# Current-Probe_Topsheet.net
KiCad netlist of a schematic drawn in Altium Designer
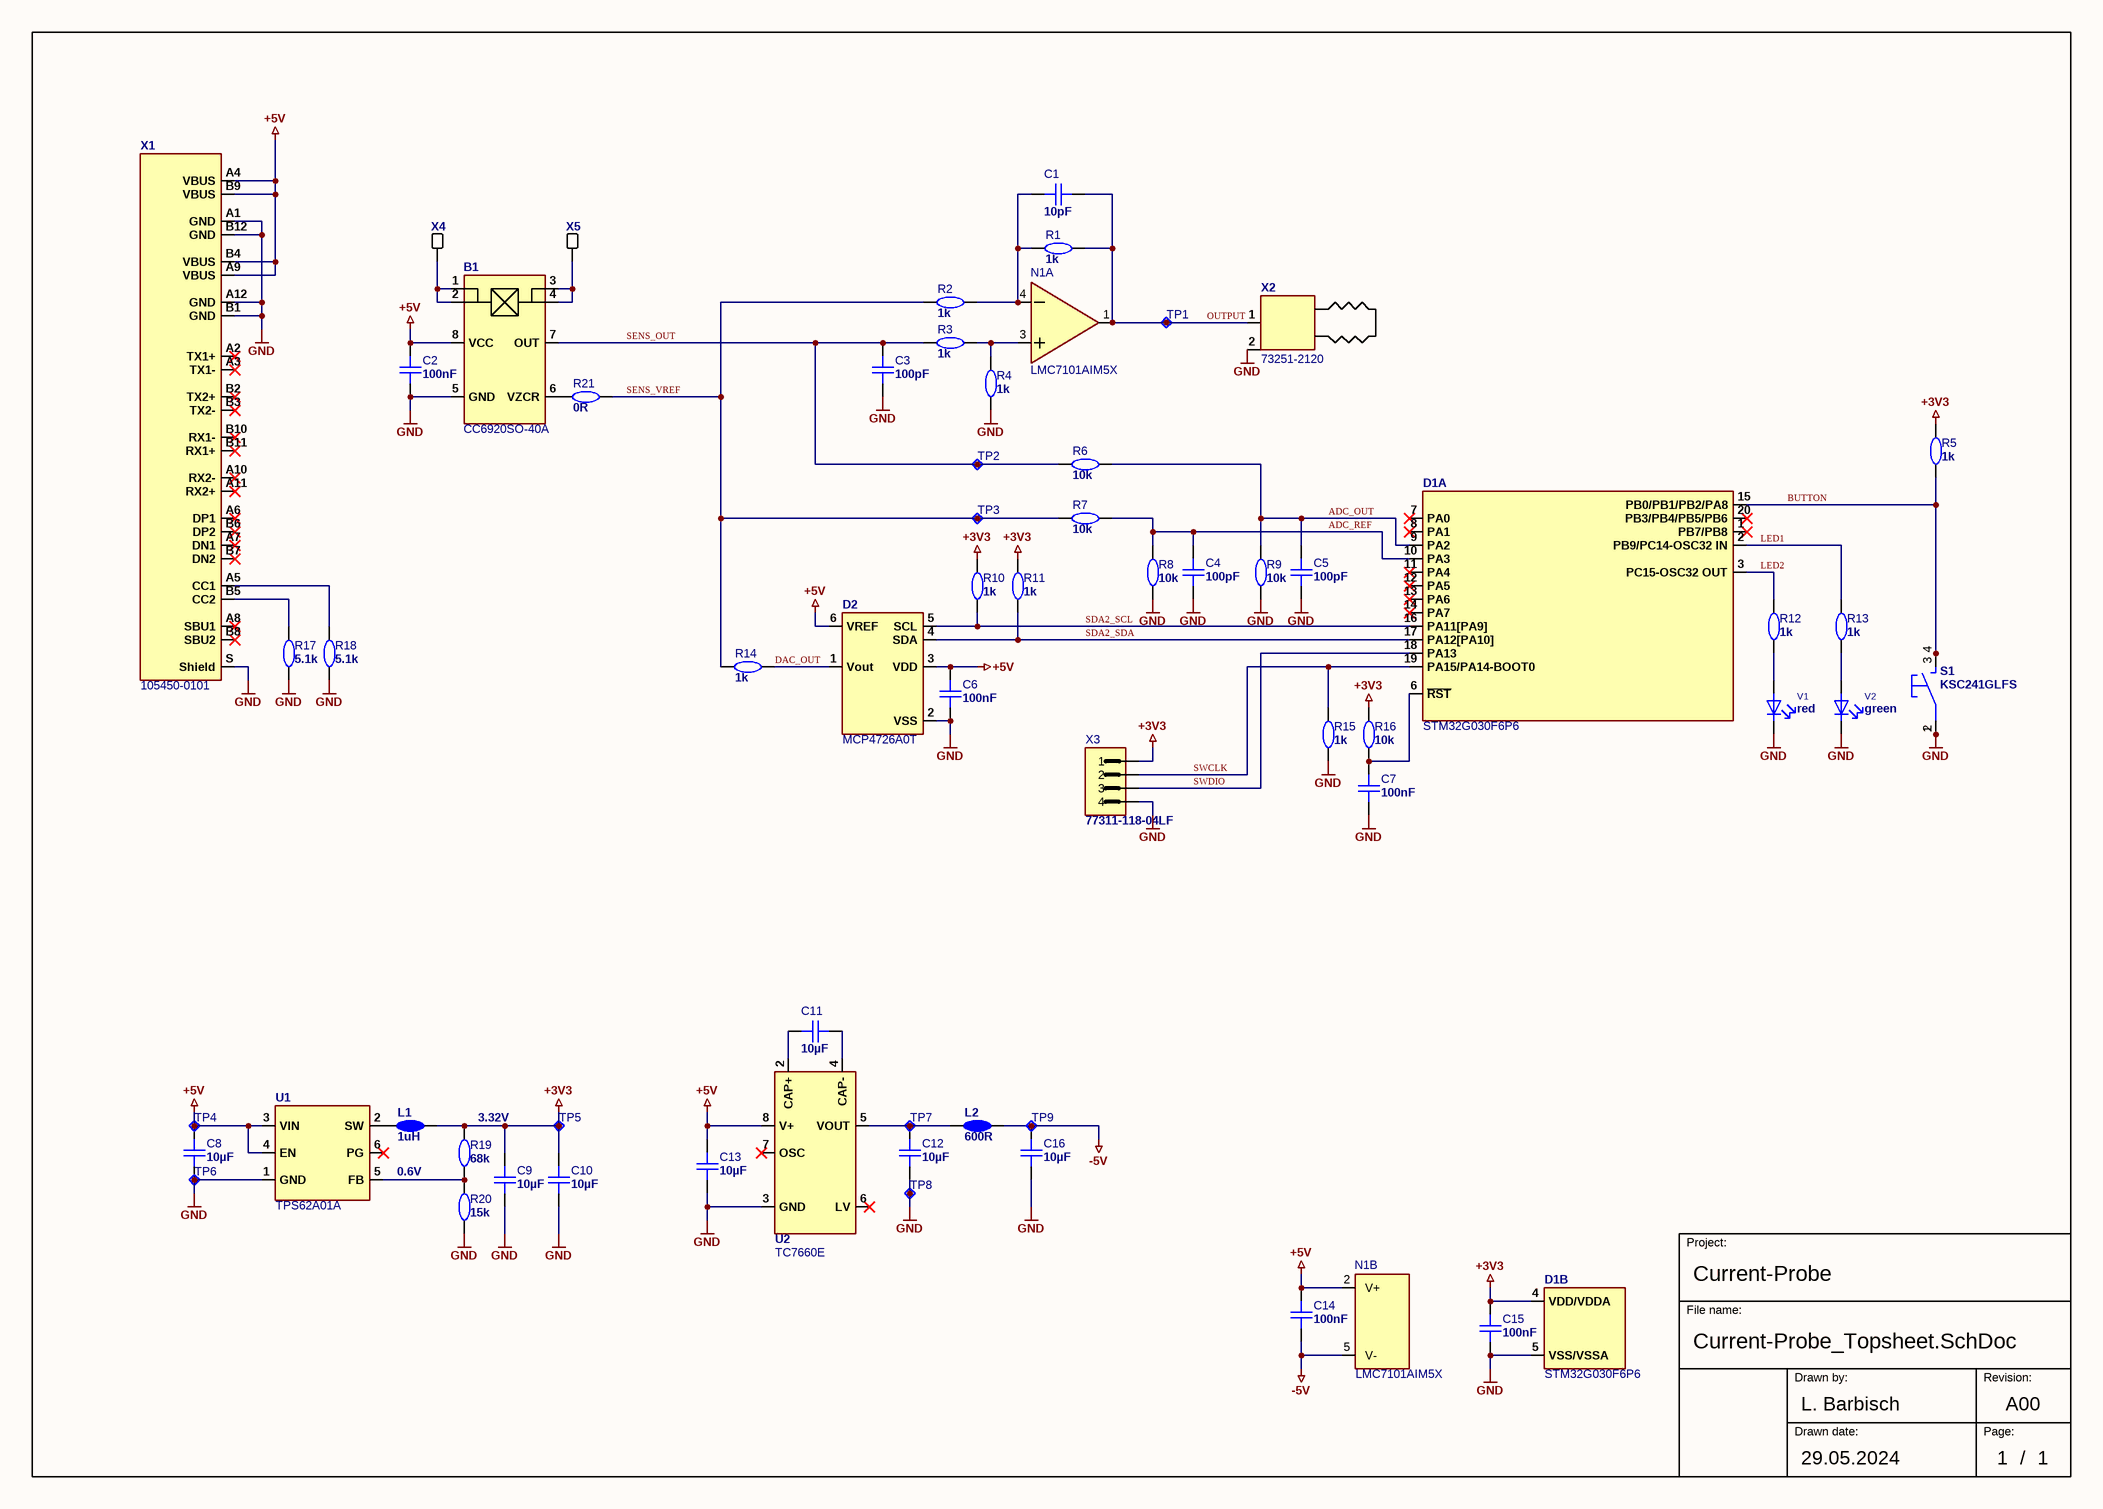
[diagram p0: Current-Probe_Topsheet.SchDoc]

(export (version "E")
  (design (tool "Eeschema 10.0.6"))
  (components
    (comp (ref "B1")
      (value "CC6920SO-40A")
      (footprint "SOIC8_N_RF")
      (description "IC Current sensor ±40A 5V")
      (fields (field (name "MANUFACTURER") "Cross chip"))
      (libsource (lib "Global Library") (part "CC6920SO-40A"))
    )
    (comp (ref "C1")
      (value "10pF")
      (footprint "C-0603_1608_095_L_RF")
      (description "Cap Cer SMD 10p 50V +/- 0.25pF  0603 C0G")
      (fields
        (field (name "MANUFACTURER PART NUMBER") "06035A100CAT*")
        (field (name "MANUFACTURER") "AVX")
        (field (name "USER") "zupa")
      )
      (libsource (lib "GPV Switzerland SA") (part "CAP"))
    )
    (comp (ref "C2")
      (value "100nF")
      (footprint "C-0603_1608_095_L_RF")
      (description "Cap Cer SMD 100n 50V 10% 0603 X7R")
      (fields
        (field (name "MANUFACTURER") "KEMET")
        (field (name "MANUFACTURER PART NUMBER") "C0603C104K5RAC")
        (field (name "USER") "epph")
      )
      (libsource (lib "GPV Switzerland SA") (part "CAP"))
    )
    (comp (ref "C3")
      (value "100pF")
      (footprint "C-0603_1608_095_L_RF")
      (description "Cap Cer SMD 100p 50V 5% 0603 C0G")
      (fields
        (field (name "MANUFACTURER PART NUMBER") "CC0603J*NPO9BN101")
        (field (name "MANUFACTURER") "YAGEO")
        (field (name "USER") "zupa")
      )
      (libsource (lib "GPV Switzerland SA") (part "CAP"))
    )
    (comp (ref "C4")
      (value "100pF")
      (footprint "C-0603_1608_095_L_RF")
      (description "Cap Cer SMD 100p 50V 5% 0603 C0G")
      (fields
        (field (name "MANUFACTURER PART NUMBER") "CC0603J*NPO9BN101")
        (field (name "MANUFACTURER") "YAGEO")
        (field (name "USER") "zupa")
      )
      (libsource (lib "GPV Switzerland SA") (part "CAP"))
    )
    (comp (ref "C5")
      (value "100pF")
      (footprint "C-0603_1608_095_L_RF")
      (description "Cap Cer SMD 100p 50V 5% 0603 C0G")
      (fields
        (field (name "MANUFACTURER PART NUMBER") "CC0603J*NPO9BN101")
        (field (name "MANUFACTURER") "YAGEO")
        (field (name "USER") "zupa")
      )
      (libsource (lib "GPV Switzerland SA") (part "CAP"))
    )
    (comp (ref "C6")
      (value "100nF")
      (footprint "C-0603_1608_095_L_RF")
      (description "Cap Cer SMD 100n 50V 10% 0603 X7R")
      (fields
        (field (name "MANUFACTURER") "KEMET")
        (field (name "MANUFACTURER PART NUMBER") "C0603C104K5RAC")
        (field (name "USER") "epph")
      )
      (libsource (lib "GPV Switzerland SA") (part "CAP"))
    )
    (comp (ref "C7")
      (value "100nF")
      (footprint "C-0603_1608_095_L_RF")
      (description "Cap Cer SMD 100n 50V 10% 0603 X7R")
      (fields
        (field (name "MANUFACTURER") "KEMET")
        (field (name "MANUFACTURER PART NUMBER") "C0603C104K5RAC")
        (field (name "USER") "epph")
      )
      (libsource (lib "GPV Switzerland SA") (part "CAP"))
    )
    (comp (ref "C8")
      (value "10µF")
      (footprint "C-0805_2012_155_L_RF")
      (description "Cap Cer SMD 10u 16V 10% 0805 X7R")
      (fields
        (field (name "MANUFACTURER") "Yageo")
        (field (name "MANUFACTURER PART NUMBER") "CC0805KKX7R7BB106")
        (field (name "USER") "epph")
      )
      (libsource (lib "GPV Switzerland SA") (part "CAP"))
    )
    (comp (ref "C9")
      (value "10µF")
      (footprint "C-0805_2012_155_L_RF")
      (description "Cap Cer SMD 10u 16V 10% 0805 X7R")
      (fields
        (field (name "MANUFACTURER") "Yageo")
        (field (name "MANUFACTURER PART NUMBER") "CC0805KKX7R7BB106")
        (field (name "USER") "epph")
      )
      (libsource (lib "GPV Switzerland SA") (part "CAP"))
    )
    (comp (ref "C10")
      (value "10µF")
      (footprint "C-0805_2012_155_L_RF")
      (description "Cap Cer SMD 10u 16V 10% 0805 X7R")
      (fields
        (field (name "MANUFACTURER") "Yageo")
        (field (name "MANUFACTURER PART NUMBER") "CC0805KKX7R7BB106")
        (field (name "USER") "epph")
      )
      (libsource (lib "GPV Switzerland SA") (part "CAP"))
    )
    (comp (ref "C11")
      (value "10µF")
      (footprint "C-0805_2012_155_L_RF")
      (description "Cap Cer SMD 10u 16V 10% 0805 X7R")
      (fields
        (field (name "MANUFACTURER") "Yageo")
        (field (name "MANUFACTURER PART NUMBER") "CC0805KKX7R7BB106")
        (field (name "USER") "epph")
      )
      (libsource (lib "GPV Switzerland SA") (part "CAP"))
    )
    (comp (ref "C12")
      (value "10µF")
      (footprint "C-0805_2012_155_L_RF")
      (description "Cap Cer SMD 10u 16V 10% 0805 X7R")
      (fields
        (field (name "MANUFACTURER") "Yageo")
        (field (name "MANUFACTURER PART NUMBER") "CC0805KKX7R7BB106")
        (field (name "USER") "epph")
      )
      (libsource (lib "GPV Switzerland SA") (part "CAP"))
    )
    (comp (ref "C13")
      (value "10µF")
      (footprint "C-0805_2012_155_L_RF")
      (description "Cap Cer SMD 10u 16V 10% 0805 X7R")
      (fields
        (field (name "MANUFACTURER") "Yageo")
        (field (name "MANUFACTURER PART NUMBER") "CC0805KKX7R7BB106")
        (field (name "USER") "epph")
      )
      (libsource (lib "GPV Switzerland SA") (part "CAP"))
    )
    (comp (ref "C14")
      (value "100nF")
      (footprint "C-0603_1608_095_L_RF")
      (description "Cap Cer SMD 100n 50V 10% 0603 X7R")
      (fields
        (field (name "MANUFACTURER") "KEMET")
        (field (name "MANUFACTURER PART NUMBER") "C0603C104K5RAC")
        (field (name "USER") "epph")
      )
      (libsource (lib "GPV Switzerland SA") (part "CAP"))
    )
    (comp (ref "C15")
      (value "100nF")
      (footprint "C-0603_1608_095_L_RF")
      (description "Cap Cer SMD 100n 50V 10% 0603 X7R")
      (fields
        (field (name "MANUFACTURER") "KEMET")
        (field (name "MANUFACTURER PART NUMBER") "C0603C104K5RAC")
        (field (name "USER") "epph")
      )
      (libsource (lib "GPV Switzerland SA") (part "CAP"))
    )
    (comp (ref "C16")
      (value "10µF")
      (footprint "C-0805_2012_155_L_RF")
      (description "Cap Cer SMD 10u 16V 10% 0805 X7R")
      (fields
        (field (name "MANUFACTURER") "Yageo")
        (field (name "MANUFACTURER PART NUMBER") "CC0805KKX7R7BB106")
        (field (name "USER") "epph")
      )
      (libsource (lib "GPV Switzerland SA") (part "CAP"))
    )
    (comp (ref "D1")
      (value "STM32G030F6P6")
      (footprint "TSSOP20_N_RF")
      (description "IC MCU Cortex M0+ 32K Flash, 8K RAM, 64MHz")
      (fields (field (name "MANUFACTURER") "ST"))
      (libsource (lib "Global Library") (part "STM32G030F6P6"))
    )
    (comp (ref "D2")
      (value "MCP4726A0T")
      (footprint "SOT23-6_N_RF")
      (description "IC DAC I2C 12Bit 2.7V-5.5V")
      (fields (field (name "MANUFACTURER") "Microchip"))
      (libsource (lib "Global Library") (part "MCP4726A0T"))
    )
    (comp (ref "L1")
      (value "1uH")
      (footprint "L_0805_N_RF")
      (description "Inductor 1uH 0.95A")
      (fields
        (field (name "MANUFACTURER") "Sunlord")
        (field (name "MANUFACTURER PART NUMBER") "MPH201210S1R0")
      )
      (libsource (lib "Global Library") (part "MPH201210S1R0"))
    )
    (comp (ref "L2")
      (value "600R")
      (footprint "L_0805_N_RF")
      (description "Ferrite Bead 600Ohm 2A 0805")
      (fields
        (field (name "MANUFACTURER") "Würth")
        (field (name "MANUFACTURER PART NUMBER") "782853611")
        (field (name "PART_VALIDATED") "Yes ¦ No")
        (field (name "FOOTPRINT_VALIDATED") "Yes ¦ No")
      )
      (libsource (lib "Global Library") (part "782853611"))
    )
    (comp (ref "N1")
      (value "LMC7101AIM5X")
      (footprint "SOT23-5_L_RF")
      (description "Low Power OP Rail to Rail")
      (fields (field (name "MANUFACTURER") "Texas Instrument") (field (name "USER") "zupa"))
      (libsource (lib "") (part "LMC7101AIM5X_1"))
    )
    (comp (ref "R1")
      (value "1k")
      (footprint "R-0603_1608_050_L_RF")
      (description "Res SMD 1k 1% 0.1W 0603")
      (fields
        (field (name "MANUFACTURER") "YAGEO")
        (field (name "MANUFACTURER PART NUMBER") "RC0603FR-071KL")
        (field (name "USER") "zupa")
      )
      (libsource (lib "GPV Switzerland SA") (part "RES"))
    )
    (comp (ref "R2")
      (value "1k")
      (footprint "R-0603_1608_050_L_RF")
      (description "Res SMD 1k 1% 0.1W 0603")
      (fields
        (field (name "MANUFACTURER") "YAGEO")
        (field (name "MANUFACTURER PART NUMBER") "RC0603FR-071KL")
        (field (name "USER") "zupa")
      )
      (libsource (lib "GPV Switzerland SA") (part "RES"))
    )
    (comp (ref "R3")
      (value "1k")
      (footprint "R-0603_1608_050_L_RF")
      (description "Res SMD 1k 1% 0.1W 0603")
      (fields
        (field (name "MANUFACTURER") "YAGEO")
        (field (name "MANUFACTURER PART NUMBER") "RC0603FR-071KL")
        (field (name "USER") "zupa")
      )
      (libsource (lib "GPV Switzerland SA") (part "RES"))
    )
    (comp (ref "R4")
      (value "1k")
      (footprint "R-0603_1608_050_L_RF")
      (description "Res SMD 1k 1% 0.1W 0603")
      (fields
        (field (name "MANUFACTURER") "YAGEO")
        (field (name "MANUFACTURER PART NUMBER") "RC0603FR-071KL")
        (field (name "USER") "zupa")
      )
      (libsource (lib "GPV Switzerland SA") (part "RES"))
    )
    (comp (ref "R5")
      (value "1k")
      (footprint "R-0603_1608_050_L_RF")
      (description "Res SMD 1k 1% 0.1W 0603")
      (fields
        (field (name "MANUFACTURER") "YAGEO")
        (field (name "MANUFACTURER PART NUMBER") "RC0603FR-071KL")
        (field (name "USER") "zupa")
      )
      (libsource (lib "GPV Switzerland SA") (part "RES"))
    )
    (comp (ref "R6")
      (value "10k")
      (footprint "R-0603_1608_050_L_RF")
      (description "Res SMD 10k 1% 0.1W 0603")
      (fields
        (field (name "MANUFACTURER") "YAGEO")
        (field (name "MANUFACTURER PART NUMBER") "RC0603FR-0710KL")
        (field (name "USER") "zupa")
      )
      (libsource (lib "GPV Switzerland SA") (part "RES"))
    )
    (comp (ref "R7")
      (value "10k")
      (footprint "R-0603_1608_050_L_RF")
      (description "Res SMD 10k 1% 0.1W 0603")
      (fields
        (field (name "MANUFACTURER") "YAGEO")
        (field (name "MANUFACTURER PART NUMBER") "RC0603FR-0710KL")
        (field (name "USER") "zupa")
      )
      (libsource (lib "GPV Switzerland SA") (part "RES"))
    )
    (comp (ref "R8")
      (value "10k")
      (footprint "R-0603_1608_050_L_RF")
      (description "Res SMD 10k 1% 0.1W 0603")
      (fields
        (field (name "MANUFACTURER") "YAGEO")
        (field (name "MANUFACTURER PART NUMBER") "RC0603FR-0710KL")
        (field (name "USER") "zupa")
      )
      (libsource (lib "GPV Switzerland SA") (part "RES"))
    )
    (comp (ref "R9")
      (value "10k")
      (footprint "R-0603_1608_050_L_RF")
      (description "Res SMD 10k 1% 0.1W 0603")
      (fields
        (field (name "MANUFACTURER") "YAGEO")
        (field (name "MANUFACTURER PART NUMBER") "RC0603FR-0710KL")
        (field (name "USER") "zupa")
      )
      (libsource (lib "GPV Switzerland SA") (part "RES"))
    )
    (comp (ref "R10")
      (value "1k")
      (footprint "R-0603_1608_050_L_RF")
      (description "Res SMD 1k 1% 0.1W 0603")
      (fields
        (field (name "MANUFACTURER") "YAGEO")
        (field (name "MANUFACTURER PART NUMBER") "RC0603FR-071KL")
        (field (name "USER") "zupa")
      )
      (libsource (lib "GPV Switzerland SA") (part "RES"))
    )
    (comp (ref "R11")
      (value "1k")
      (footprint "R-0603_1608_050_L_RF")
      (description "Res SMD 1k 1% 0.1W 0603")
      (fields
        (field (name "MANUFACTURER") "YAGEO")
        (field (name "MANUFACTURER PART NUMBER") "RC0603FR-071KL")
        (field (name "USER") "zupa")
      )
      (libsource (lib "GPV Switzerland SA") (part "RES"))
    )
    (comp (ref "R12")
      (value "1k")
      (footprint "R-0603_1608_050_L_RF")
      (description "Res SMD 1k 1% 0.1W 0603")
      (fields
        (field (name "MANUFACTURER") "YAGEO")
        (field (name "MANUFACTURER PART NUMBER") "RC0603FR-071KL")
        (field (name "USER") "zupa")
      )
      (libsource (lib "GPV Switzerland SA") (part "RES"))
    )
    (comp (ref "R13")
      (value "1k")
      (footprint "R-0603_1608_050_L_RF")
      (description "Res SMD 1k 1% 0.1W 0603")
      (fields
        (field (name "MANUFACTURER") "YAGEO")
        (field (name "MANUFACTURER PART NUMBER") "RC0603FR-071KL")
        (field (name "USER") "zupa")
      )
      (libsource (lib "GPV Switzerland SA") (part "RES"))
    )
    (comp (ref "R14")
      (value "1k")
      (footprint "R-0603_1608_050_L_RF")
      (description "Res SMD 1k 1% 0.1W 0603")
      (fields
        (field (name "MANUFACTURER") "YAGEO")
        (field (name "MANUFACTURER PART NUMBER") "RC0603FR-071KL")
        (field (name "USER") "zupa")
      )
      (libsource (lib "GPV Switzerland SA") (part "RES"))
    )
    (comp (ref "R15")
      (value "1k")
      (footprint "R-0603_1608_050_L_RF")
      (description "Res SMD 1k 1% 0.1W 0603")
      (fields
        (field (name "MANUFACTURER") "YAGEO")
        (field (name "MANUFACTURER PART NUMBER") "RC0603FR-071KL")
        (field (name "USER") "zupa")
      )
      (libsource (lib "GPV Switzerland SA") (part "RES"))
    )
    (comp (ref "R16")
      (value "10k")
      (footprint "R-0603_1608_050_L_RF")
      (description "Res SMD 10k 1% 0.1W 0603")
      (fields
        (field (name "MANUFACTURER") "YAGEO")
        (field (name "MANUFACTURER PART NUMBER") "RC0603FR-0710KL")
        (field (name "USER") "zupa")
      )
      (libsource (lib "GPV Switzerland SA") (part "RES"))
    )
    (comp (ref "R17")
      (value "5.1k")
      (footprint "R-0603_1608_050_L_RF")
      (description "Res SMD 5k1 1% 0.1W 0603")
      (fields
        (field (name "MANUFACTURER PART NUMBER") "RC0603FR-075K1L")
        (field (name "MANUFACTURER") "YAGEO")
        (field (name "USER") "napa")
      )
      (libsource (lib "GPV Switzerland SA") (part "RES"))
    )
    (comp (ref "R18")
      (value "5.1k")
      (footprint "R-0603_1608_050_L_RF")
      (description "Res SMD 5k1 1% 0.1W 0603")
      (fields
        (field (name "MANUFACTURER PART NUMBER") "RC0603FR-075K1L")
        (field (name "MANUFACTURER") "YAGEO")
        (field (name "USER") "napa")
      )
      (libsource (lib "GPV Switzerland SA") (part "RES"))
    )
    (comp (ref "R19")
      (value "68k")
      (footprint "R-0603_1608_050_L_RF")
      (description "Res SMD 68k 1% 0.1W 0603")
      (fields
        (field (name "MANUFACTURER PART NUMBER") "RC0603FR-0768KL")
        (field (name "MANUFACTURER") "YAGEO")
        (field (name "USER") "zupa")
      )
      (libsource (lib "GPV Switzerland SA") (part "RES"))
    )
    (comp (ref "R20")
      (value "15k")
      (footprint "R-0603_1608_050_L_RF")
      (description "Res SMD 15k 1% 0.1W 0603")
      (fields
        (field (name "MANUFACTURER") "YAGEO")
        (field (name "MANUFACTURER PART NUMBER") "RC0603FR-0715KL")
        (field (name "USER") "zupa")
      )
      (libsource (lib "GPV Switzerland SA") (part "RES"))
    )
    (comp (ref "R21")
      (value "0R")
      (footprint "R-0603_1608_050_L_RF")
      (description "Res SMD 0R 0.1W 0603")
      (fields
        (field (name "MANUFACTURER PART NUMBER") "RK73Z1JT**")
        (field (name "MANUFACTURER") "KOA")
        (field (name "USER") "zupa")
      )
      (libsource (lib "GPV Switzerland SA") (part "RES"))
    )
    (comp (ref "S1")
      (value "KSC241GLFS")
      (footprint "S-0062x0062_R_P0890_C&K-KSC-241G-LFS")
      (description "Switch Tactile N.O. SPST Round Button Gull Wing 0.05A 32VDC 1VA 300000Cycle 4N SMD T/R")
      (fields
        (field (name "MANUFACTURER") "ITT C&K")
        (field (name "SOURCE") "Tischstation_BWE_Part_Prj.SchLib")
      )
      (libsource (lib "GPV Switzerland SA") (part "KSC241GLFS"))
    )
    (comp (ref "TP1")
      (value "TestPoint 1.0mm")
      (footprint "TP_1.0mm")
      (fields (field (name "USER") "zupa"))
      (libsource (lib "GPV Switzerland SA") (part "Testpoint"))
    )
    (comp (ref "TP2")
      (value "TestPoint 1.0mm")
      (footprint "TP_1.0mm")
      (fields (field (name "USER") "zupa"))
      (libsource (lib "GPV Switzerland SA") (part "Testpoint"))
    )
    (comp (ref "TP3")
      (value "TestPoint 1.0mm")
      (footprint "TP_1.0mm")
      (fields (field (name "USER") "zupa"))
      (libsource (lib "GPV Switzerland SA") (part "Testpoint"))
    )
    (comp (ref "TP4")
      (value "TestPoint 1.0mm")
      (footprint "TP_1.0mm")
      (fields (field (name "USER") "zupa"))
      (libsource (lib "GPV Switzerland SA") (part "Testpoint"))
    )
    (comp (ref "TP5")
      (value "TestPoint 1.0mm")
      (footprint "TP_1.0mm")
      (fields (field (name "USER") "zupa"))
      (libsource (lib "GPV Switzerland SA") (part "Testpoint"))
    )
    (comp (ref "TP6")
      (value "TestPoint 1.0mm")
      (footprint "TP_1.0mm")
      (fields (field (name "USER") "zupa"))
      (libsource (lib "GPV Switzerland SA") (part "Testpoint"))
    )
    (comp (ref "TP7")
      (value "TestPoint 1.0mm")
      (footprint "TP_1.0mm")
      (fields (field (name "USER") "zupa"))
      (libsource (lib "GPV Switzerland SA") (part "Testpoint"))
    )
    (comp (ref "TP8")
      (value "TestPoint 1.0mm")
      (footprint "TP_1.0mm")
      (fields (field (name "USER") "zupa"))
      (libsource (lib "GPV Switzerland SA") (part "Testpoint"))
    )
    (comp (ref "TP9")
      (value "TestPoint 1.0mm")
      (footprint "TP_1.0mm")
      (fields (field (name "USER") "zupa"))
      (libsource (lib "GPV Switzerland SA") (part "Testpoint"))
    )
    (comp (ref "U1")
      (value "TPS62A01A")
      (footprint "SOT-563_N_RF")
      (description "IC BUCK 1A 2.5-5.5Vin 2.4MHz")
      (fields (field (name "MANUFACTURER") "TI") (field (name "MANUFACTURER PART NUMBER") "TPS62A01ADRLR"))
      (libsource (lib "Global Library") (part "TPS62A01A"))
    )
    (comp (ref "U2")
      (value "TC7660E")
      (footprint "SOIC8_N_RF")
      (description "IC REG Charge Pump negative")
      (fields (field (name "MANUFACTURER") "Microchip"))
      (libsource (lib "Global Library") (part "TC7660E"))
    )
    (comp (ref "V1")
      (value "red")
      (footprint "LED-0603_1608_Red_L_RF")
      (description "LED Red LTST-C190KRKT 0603")
      (fields
        (field (name "MANUFACTURER PART NUMBER") "LTST-C190KRKT")
        (field (name "MANUFACTURER") "Lite-On Inc")
        (field (name "USER") "epph")
      )
      (libsource (lib "GPV Switzerland SA") (part "LED"))
    )
    (comp (ref "V2")
      (value "green")
      (footprint "LED-0603_1608_Green_L_RF")
      (description "LED Green LTST-C190KGKT 0603")
      (fields
        (field (name "MANUFACTURER") "Lite-On Inc")
        (field (name "MANUFACTURER PART NUMBER") "LTST-C190KGKT")
        (field (name "USER") "epph")
      )
      (libsource (lib "GPV Switzerland SA") (part "LED"))
    )
    (comp (ref "X1")
      (value "105450-0101")
      (footprint "105450-0101")
      (description "CONN USB-C 16pin")
      (fields (field (name "MANUFACTURER") "Molex"))
      (libsource (lib "Global Library") (part "105450-0101"))
    )
    (comp (ref "X2")
      (value "73251-2120")
      (footprint "73251-2120")
      (description "CONN RF SMA")
      (fields (field (name "MANUFACTURER") "MOLEX"))
      (libsource (lib "Global Library") (part "73251-2120"))
    )
    (comp (ref "X3")
      (value "77311-118-04LF")
      (footprint "X-0101X0025_R_FCI_77311-118-04LF")
      (description "CONN HEADER 4POS 1ROW THT 2.54MM FCI 77311-118-04LF")
      (fields
        (field (name "MANUFACTURER") "FCI")
        (field (name "Comment") "CONN HEADER 4POS 1ROW THT 2.54MM")
        (field (name "USER") "zupa")
      )
      (libsource (lib "GPV Switzerland SA") (part "Connector-4P"))
    )
    (comp (ref "X4")
      (value "~")
      (footprint "Lötpad_2x3")
      (description "Solderpad 2mm x 3mm")
      (libsource (lib "Global Library") (part "Lötpad_2mmx3mm"))
    )
    (comp (ref "X5")
      (value "~")
      (footprint "Lötpad_2x3")
      (description "Solderpad 2mm x 3mm")
      (libsource (lib "Global Library") (part "Lötpad_2mmx3mm"))
    )
  )
  (nets
    (net (code "1") (name "+3V3") (class "Default")
      (node (ref "C10") (pin "2") (pinfunction "2_2") (pintype "passive"))
      (node (ref "C15") (pin "2") (pinfunction "2_2") (pintype "passive"))
      (node (ref "C9") (pin "2") (pinfunction "2_2") (pintype "passive"))
      (node (ref "D1") (pin "4") (pinfunction "VDD/VDDA_4") (pintype "passive"))
      (node (ref "L1") (pin "2") (pinfunction "2_2") (pintype "passive"))
      (node (ref "R10") (pin "2") (pinfunction "2_2") (pintype "passive"))
      (node (ref "R11") (pin "2") (pinfunction "2_2") (pintype "passive"))
      (node (ref "R16") (pin "2") (pinfunction "2_2") (pintype "passive"))
      (node (ref "R19") (pin "2") (pinfunction "2_2") (pintype "passive"))
      (node (ref "R5") (pin "2") (pinfunction "2_2") (pintype "passive"))
      (node (ref "TP5") (pin "1") (pinfunction "1_1") (pintype "passive"))
      (node (ref "X3") (pin "1") (pinfunction "1_1") (pintype "passive"))
    )
    (net (code "2") (name "+5V") (class "Default")
      (node (ref "B1") (pin "8") (pinfunction "VCC_8") (pintype "passive"))
      (node (ref "C13") (pin "2") (pinfunction "2_2") (pintype "passive"))
      (node (ref "C14") (pin "2") (pinfunction "2_2") (pintype "passive"))
      (node (ref "C2") (pin "2") (pinfunction "2_2") (pintype "passive"))
      (node (ref "C6") (pin "2") (pinfunction "2_2") (pintype "passive"))
      (node (ref "C8") (pin "2") (pinfunction "2_2") (pintype "passive"))
      (node (ref "D2") (pin "3") (pinfunction "VDD_3") (pintype "passive"))
      (node (ref "D2") (pin "6") (pinfunction "VREF_6") (pintype "passive"))
      (node (ref "N1") (pin "2") (pinfunction "V+_2") (pintype "passive"))
      (node (ref "TP4") (pin "1") (pinfunction "1_1") (pintype "passive"))
      (node (ref "U1") (pin "3") (pinfunction "VIN_3") (pintype "passive"))
      (node (ref "U1") (pin "4") (pinfunction "EN_4") (pintype "passive"))
      (node (ref "U2") (pin "8") (pinfunction "V+_8") (pintype "passive"))
      (node (ref "X1") (pin "A4") (pinfunction "VBUS_A4") (pintype "passive"))
      (node (ref "X1") (pin "A9") (pinfunction "VBUS_A9") (pintype "passive"))
      (node (ref "X1") (pin "B4") (pinfunction "VBUS_B4") (pintype "passive"))
      (node (ref "X1") (pin "B9") (pinfunction "VBUS_B9") (pintype "passive"))
    )
    (net (code "3") (name "-5V") (class "Default")
      (node (ref "C14") (pin "1") (pinfunction "1_1") (pintype "passive"))
      (node (ref "C16") (pin "2") (pinfunction "2_2") (pintype "passive"))
      (node (ref "L2") (pin "2") (pinfunction "2_2") (pintype "passive"))
      (node (ref "N1") (pin "5") (pinfunction "V-_5") (pintype "passive"))
      (node (ref "TP9") (pin "1") (pinfunction "1_1") (pintype "passive"))
    )
    (net (code "4") (name "/ADC_OUT") (class "Default")
      (node (ref "C5") (pin "2") (pinfunction "2_2") (pintype "passive"))
      (node (ref "D1") (pin "9") (pinfunction "PA2_9") (pintype "passive"))
      (node (ref "R6") (pin "2") (pinfunction "2_2") (pintype "passive"))
      (node (ref "R9") (pin "2") (pinfunction "2_2") (pintype "passive"))
    )
    (net (code "5") (name "/ADC_REF") (class "Default")
      (node (ref "C4") (pin "2") (pinfunction "2_2") (pintype "passive"))
      (node (ref "D1") (pin "10") (pinfunction "PA3_10") (pintype "passive"))
      (node (ref "R7") (pin "2") (pinfunction "2_2") (pintype "passive"))
      (node (ref "R8") (pin "2") (pinfunction "2_2") (pintype "passive"))
    )
    (net (code "6") (name "/BUTTON") (class "Default")
      (node (ref "D1") (pin "15") (pinfunction "PB0/PB1/PB2/PA8_15") (pintype "passive"))
      (node (ref "R5") (pin "1") (pinfunction "1_1") (pintype "passive"))
      (node (ref "S1") (pin "3") (pintype "passive"))
      (node (ref "S1") (pin "4") (pintype "passive"))
    )
    (net (code "7") (name "/DAC_OUT") (class "Default")
      (node (ref "D2") (pin "1") (pinfunction "Vout_1") (pintype "passive"))
      (node (ref "R14") (pin "2") (pinfunction "2_2") (pintype "passive"))
    )
    (net (code "8") (name "/LED1") (class "Default")
      (node (ref "D1") (pin "2") (pinfunction "PB9/PC14-OSC32_IN_2") (pintype "passive"))
      (node (ref "R13") (pin "2") (pinfunction "2_2") (pintype "passive"))
    )
    (net (code "9") (name "/LED2") (class "Default")
      (node (ref "D1") (pin "3") (pinfunction "PC15-OSC32_OUT_3") (pintype "passive"))
      (node (ref "R12") (pin "2") (pinfunction "2_2") (pintype "passive"))
    )
    (net (code "10") (name "/OUTPUT") (class "Default")
      (node (ref "C1") (pin "2") (pinfunction "2_2") (pintype "passive"))
      (node (ref "N1") (pin "1") (pintype "passive"))
      (node (ref "R1") (pin "2") (pinfunction "2_2") (pintype "passive"))
      (node (ref "TP1") (pin "1") (pinfunction "1_1") (pintype "passive"))
      (node (ref "X2") (pin "1") (pintype "passive"))
    )
    (net (code "11") (name "/SDA2_SCL") (class "Default")
      (node (ref "D1") (pin "16") (pinfunction "PA11[PA9]_16") (pintype "passive"))
      (node (ref "D2") (pin "5") (pinfunction "SCL_5") (pintype "passive"))
      (node (ref "R10") (pin "1") (pinfunction "1_1") (pintype "passive"))
    )
    (net (code "12") (name "/SDA2_SDA") (class "Default")
      (node (ref "D1") (pin "17") (pinfunction "PA12[PA10]_17") (pintype "passive"))
      (node (ref "D2") (pin "4") (pinfunction "SDA_4") (pintype "passive"))
      (node (ref "R11") (pin "1") (pinfunction "1_1") (pintype "passive"))
    )
    (net (code "13") (name "/SENS_OUT") (class "Default")
      (node (ref "B1") (pin "7") (pinfunction "OUT_7") (pintype "passive"))
      (node (ref "C3") (pin "2") (pinfunction "2_2") (pintype "passive"))
      (node (ref "R3") (pin "1") (pinfunction "1_1") (pintype "passive"))
      (node (ref "R6") (pin "1") (pinfunction "1_1") (pintype "passive"))
      (node (ref "TP2") (pin "1") (pinfunction "1_1") (pintype "passive"))
    )
    (net (code "14") (name "/SENS_VREF") (class "Default")
      (node (ref "R14") (pin "1") (pinfunction "1_1") (pintype "passive"))
      (node (ref "R2") (pin "1") (pinfunction "1_1") (pintype "passive"))
      (node (ref "R21") (pin "2") (pinfunction "2_2") (pintype "passive"))
      (node (ref "R7") (pin "1") (pinfunction "1_1") (pintype "passive"))
      (node (ref "TP3") (pin "1") (pinfunction "1_1") (pintype "passive"))
    )
    (net (code "15") (name "/SWCLK") (class "Default")
      (node (ref "D1") (pin "19") (pinfunction "PA15/PA14-BOOT0_19") (pintype "passive"))
      (node (ref "R15") (pin "2") (pinfunction "2_2") (pintype "passive"))
      (node (ref "X3") (pin "2") (pinfunction "2_2") (pintype "passive"))
    )
    (net (code "16") (name "/SWDIO") (class "Default")
      (node (ref "D1") (pin "18") (pinfunction "PA13_18") (pintype "passive"))
      (node (ref "X3") (pin "3") (pinfunction "3_3") (pintype "passive"))
    )
    (net (code "17") (name "GND") (class "Default")
      (node (ref "B1") (pin "5") (pinfunction "GND_5") (pintype "passive"))
      (node (ref "C10") (pin "1") (pinfunction "1_1") (pintype "passive"))
      (node (ref "C12") (pin "1") (pinfunction "1_1") (pintype "passive"))
      (node (ref "C13") (pin "1") (pinfunction "1_1") (pintype "passive"))
      (node (ref "C15") (pin "1") (pinfunction "1_1") (pintype "passive"))
      (node (ref "C16") (pin "1") (pinfunction "1_1") (pintype "passive"))
      (node (ref "C2") (pin "1") (pinfunction "1_1") (pintype "passive"))
      (node (ref "C3") (pin "1") (pinfunction "1_1") (pintype "passive"))
      (node (ref "C4") (pin "1") (pinfunction "1_1") (pintype "passive"))
      (node (ref "C5") (pin "1") (pinfunction "1_1") (pintype "passive"))
      (node (ref "C6") (pin "1") (pinfunction "1_1") (pintype "passive"))
      (node (ref "C7") (pin "1") (pinfunction "1_1") (pintype "passive"))
      (node (ref "C8") (pin "1") (pinfunction "1_1") (pintype "passive"))
      (node (ref "C9") (pin "1") (pinfunction "1_1") (pintype "passive"))
      (node (ref "D1") (pin "5") (pinfunction "VSS/VSSA_5") (pintype "passive"))
      (node (ref "D2") (pin "2") (pinfunction "VSS_2") (pintype "passive"))
      (node (ref "R15") (pin "1") (pinfunction "1_1") (pintype "passive"))
      (node (ref "R17") (pin "1") (pinfunction "1_1") (pintype "passive"))
      (node (ref "R18") (pin "1") (pinfunction "1_1") (pintype "passive"))
      (node (ref "R20") (pin "1") (pinfunction "1_1") (pintype "passive"))
      (node (ref "R4") (pin "2") (pinfunction "2_2") (pintype "passive"))
      (node (ref "R8") (pin "1") (pinfunction "1_1") (pintype "passive"))
      (node (ref "R9") (pin "1") (pinfunction "1_1") (pintype "passive"))
      (node (ref "S1") (pin "1") (pintype "passive"))
      (node (ref "S1") (pin "2") (pintype "passive"))
      (node (ref "TP6") (pin "1") (pinfunction "1_1") (pintype "passive"))
      (node (ref "TP8") (pin "1") (pinfunction "1_1") (pintype "passive"))
      (node (ref "U1") (pin "1") (pinfunction "GND_1") (pintype "passive"))
      (node (ref "U2") (pin "3") (pinfunction "GND_3") (pintype "passive"))
      (node (ref "V1") (pin "2") (pinfunction "2_2") (pintype "passive"))
      (node (ref "V2") (pin "2") (pinfunction "2_2") (pintype "passive"))
      (node (ref "X1") (pin "A1") (pinfunction "GND_A1") (pintype "passive"))
      (node (ref "X1") (pin "A12") (pinfunction "GND_A12") (pintype "passive"))
      (node (ref "X1") (pin "B1") (pinfunction "GND_B1") (pintype "passive"))
      (node (ref "X1") (pin "B12") (pinfunction "GND_B12") (pintype "passive"))
      (node (ref "X1") (pin "S") (pinfunction "Shield_S") (pintype "passive"))
      (node (ref "X2") (pin "2") (pintype "passive"))
      (node (ref "X3") (pin "4") (pinfunction "4_4") (pintype "passive"))
    )
    (net (code "18") (name "Net-(B1-IP+-Pad1)") (class "Default")
      (node (ref "B1") (pin "1") (pinfunction "IP+_1") (pintype "passive"))
      (node (ref "B1") (pin "2") (pinfunction "IP+_2") (pintype "passive"))
      (node (ref "X4") (pin "1") (pintype "passive"))
    )
    (net (code "19") (name "Net-(B1-IP--Pad3)") (class "Default")
      (node (ref "B1") (pin "3") (pinfunction "IP-_3") (pintype "passive"))
      (node (ref "B1") (pin "4") (pinfunction "IP-_4") (pintype "passive"))
      (node (ref "X5") (pin "1") (pintype "passive"))
    )
    (net (code "20") (name "Net-(B1-VZCR)") (class "Default")
      (node (ref "B1") (pin "6") (pinfunction "VZCR_6") (pintype "passive"))
      (node (ref "R21") (pin "1") (pinfunction "1_1") (pintype "passive"))
    )
    (net (code "21") (name "Net-(C1-Pad1)") (class "Default")
      (node (ref "C1") (pin "1") (pinfunction "1_1") (pintype "passive"))
      (node (ref "N1") (pin "4") (pintype "passive"))
      (node (ref "R1") (pin "1") (pinfunction "1_1") (pintype "passive"))
      (node (ref "R2") (pin "2") (pinfunction "2_2") (pintype "passive"))
    )
    (net (code "22") (name "Net-(D1A-~{RST})") (class "Default")
      (node (ref "C7") (pin "2") (pinfunction "2_2") (pintype "passive"))
      (node (ref "D1") (pin "6") (pinfunction "~{RST}_6") (pintype "passive"))
      (node (ref "R16") (pin "1") (pinfunction "1_1") (pintype "passive"))
    )
    (net (code "23") (name "Net-(N1-Pad3)") (class "Default")
      (node (ref "N1") (pin "3") (pintype "passive"))
      (node (ref "R3") (pin "2") (pinfunction "2_2") (pintype "passive"))
      (node (ref "R4") (pin "1") (pinfunction "1_1") (pintype "passive"))
    )
    (net (code "24") (name "Net-(R12-Pad1)") (class "Default")
      (node (ref "R12") (pin "1") (pinfunction "1_1") (pintype "passive"))
      (node (ref "V1") (pin "1") (pinfunction "1_1") (pintype "passive"))
    )
    (net (code "25") (name "Net-(R13-Pad1)") (class "Default")
      (node (ref "R13") (pin "1") (pinfunction "1_1") (pintype "passive"))
      (node (ref "V2") (pin "1") (pinfunction "1_1") (pintype "passive"))
    )
    (net (code "26") (name "Net-(U1-FB)") (class "Default")
      (node (ref "R19") (pin "1") (pinfunction "1_1") (pintype "passive"))
      (node (ref "R20") (pin "2") (pinfunction "2_2") (pintype "passive"))
      (node (ref "U1") (pin "5") (pinfunction "FB_5") (pintype "passive"))
    )
    (net (code "27") (name "Net-(U1-SW)") (class "Default")
      (node (ref "L1") (pin "1") (pinfunction "1_1") (pintype "passive"))
      (node (ref "U1") (pin "2") (pinfunction "SW_2") (pintype "passive"))
    )
    (net (code "28") (name "Net-(U2-CAP+)") (class "Default")
      (node (ref "C11") (pin "2") (pinfunction "2_2") (pintype "passive"))
      (node (ref "U2") (pin "2") (pinfunction "CAP+_2") (pintype "passive"))
    )
    (net (code "29") (name "Net-(U2-CAP-)") (class "Default")
      (node (ref "C11") (pin "1") (pinfunction "1_1") (pintype "passive"))
      (node (ref "U2") (pin "4") (pinfunction "CAP-_4") (pintype "passive"))
    )
    (net (code "30") (name "Net-(U2-VOUT)") (class "Default")
      (node (ref "C12") (pin "2") (pinfunction "2_2") (pintype "passive"))
      (node (ref "L2") (pin "1") (pinfunction "1_1") (pintype "passive"))
      (node (ref "TP7") (pin "1") (pinfunction "1_1") (pintype "passive"))
      (node (ref "U2") (pin "5") (pinfunction "VOUT_5") (pintype "passive"))
    )
    (net (code "31") (name "Net-(X1-CC1)") (class "Default")
      (node (ref "R18") (pin "2") (pinfunction "2_2") (pintype "passive"))
      (node (ref "X1") (pin "A5") (pinfunction "CC1_A5") (pintype "passive"))
    )
    (net (code "32") (name "Net-(X1-CC2)") (class "Default")
      (node (ref "R17") (pin "2") (pinfunction "2_2") (pintype "passive"))
      (node (ref "X1") (pin "B5") (pinfunction "CC2_B5") (pintype "passive"))
    )
    (net (code "33") (name "unconnected-(D1A-PA0-Pad7)") (class "Default")
      (node (ref "D1") (pin "7") (pinfunction "PA0_7") (pintype "passive+no_connect"))
    )
    (net (code "34") (name "unconnected-(D1A-PA1-Pad8)") (class "Default")
      (node (ref "D1") (pin "8") (pinfunction "PA1_8") (pintype "passive+no_connect"))
    )
    (net (code "35") (name "unconnected-(D1A-PA4-Pad11)") (class "Default")
      (node (ref "D1") (pin "11") (pinfunction "PA4_11") (pintype "passive+no_connect"))
    )
    (net (code "36") (name "unconnected-(D1A-PA5-Pad12)") (class "Default")
      (node (ref "D1") (pin "12") (pinfunction "PA5_12") (pintype "passive+no_connect"))
    )
    (net (code "37") (name "unconnected-(D1A-PA6-Pad13)") (class "Default")
      (node (ref "D1") (pin "13") (pinfunction "PA6_13") (pintype "passive+no_connect"))
    )
    (net (code "38") (name "unconnected-(D1A-PA7-Pad14)") (class "Default")
      (node (ref "D1") (pin "14") (pinfunction "PA7_14") (pintype "passive+no_connect"))
    )
    (net (code "39") (name "unconnected-(D1A-PB3{slash}PB4{slash}PB5{slash}PB6-Pad20)") (class "Default")
      (node (ref "D1") (pin "20") (pinfunction "PB3/PB4/PB5/PB6_20") (pintype "passive+no_connect"))
    )
    (net (code "40") (name "unconnected-(D1A-PB7{slash}PB8-Pad1)") (class "Default")
      (node (ref "D1") (pin "1") (pinfunction "PB7/PB8_1") (pintype "passive+no_connect"))
    )
    (net (code "41") (name "unconnected-(U1-PG-Pad6)") (class "Default")
      (node (ref "U1") (pin "6") (pinfunction "PG_6") (pintype "passive+no_connect"))
    )
    (net (code "42") (name "unconnected-(U2-LV-Pad6)") (class "Default")
      (node (ref "U2") (pin "6") (pinfunction "LV_6") (pintype "passive+no_connect"))
    )
    (net (code "43") (name "unconnected-(U2-OSC-Pad7)") (class "Default")
      (node (ref "U2") (pin "7") (pinfunction "OSC_7") (pintype "passive+no_connect"))
    )
    (net (code "44") (name "unconnected-(X1-DN1-PadA7)") (class "Default")
      (node (ref "X1") (pin "A7") (pinfunction "DN1_A7") (pintype "passive+no_connect"))
    )
    (net (code "45") (name "unconnected-(X1-DN2-PadB7)") (class "Default")
      (node (ref "X1") (pin "B7") (pinfunction "DN2_B7") (pintype "passive+no_connect"))
    )
    (net (code "46") (name "unconnected-(X1-DP1-PadA6)") (class "Default")
      (node (ref "X1") (pin "A6") (pinfunction "DP1_A6") (pintype "passive+no_connect"))
    )
    (net (code "47") (name "unconnected-(X1-DP2-PadB6)") (class "Default")
      (node (ref "X1") (pin "B6") (pinfunction "DP2_B6") (pintype "passive+no_connect"))
    )
    (net (code "48") (name "unconnected-(X1-RX1+-PadB11)") (class "Default")
      (node (ref "X1") (pin "B11") (pinfunction "RX1+_B11") (pintype "passive+no_connect"))
    )
    (net (code "49") (name "unconnected-(X1-RX1--PadB10)") (class "Default")
      (node (ref "X1") (pin "B10") (pinfunction "RX1-_B10") (pintype "passive+no_connect"))
    )
    (net (code "50") (name "unconnected-(X1-RX2+-PadA11)") (class "Default")
      (node (ref "X1") (pin "A11") (pinfunction "RX2+_A11") (pintype "passive+no_connect"))
    )
    (net (code "51") (name "unconnected-(X1-RX2--PadA10)") (class "Default")
      (node (ref "X1") (pin "A10") (pinfunction "RX2-_A10") (pintype "passive+no_connect"))
    )
    (net (code "52") (name "unconnected-(X1-SBU1-PadA8)") (class "Default")
      (node (ref "X1") (pin "A8") (pinfunction "SBU1_A8") (pintype "passive+no_connect"))
    )
    (net (code "53") (name "unconnected-(X1-SBU2-PadB8)") (class "Default")
      (node (ref "X1") (pin "B8") (pinfunction "SBU2_B8") (pintype "passive+no_connect"))
    )
    (net (code "54") (name "unconnected-(X1-TX1+-PadA2)") (class "Default")
      (node (ref "X1") (pin "A2") (pinfunction "TX1+_A2") (pintype "passive+no_connect"))
    )
    (net (code "55") (name "unconnected-(X1-TX1--PadA3)") (class "Default")
      (node (ref "X1") (pin "A3") (pinfunction "TX1-_A3") (pintype "passive+no_connect"))
    )
    (net (code "56") (name "unconnected-(X1-TX2+-PadB2)") (class "Default")
      (node (ref "X1") (pin "B2") (pinfunction "TX2+_B2") (pintype "passive+no_connect"))
    )
    (net (code "57") (name "unconnected-(X1-TX2--PadB3)") (class "Default")
      (node (ref "X1") (pin "B3") (pinfunction "TX2-_B3") (pintype "passive+no_connect"))
    )
  )
)
